# NT_MCUModule.net
KiCad netlist of a schematic drawn in EAGLE
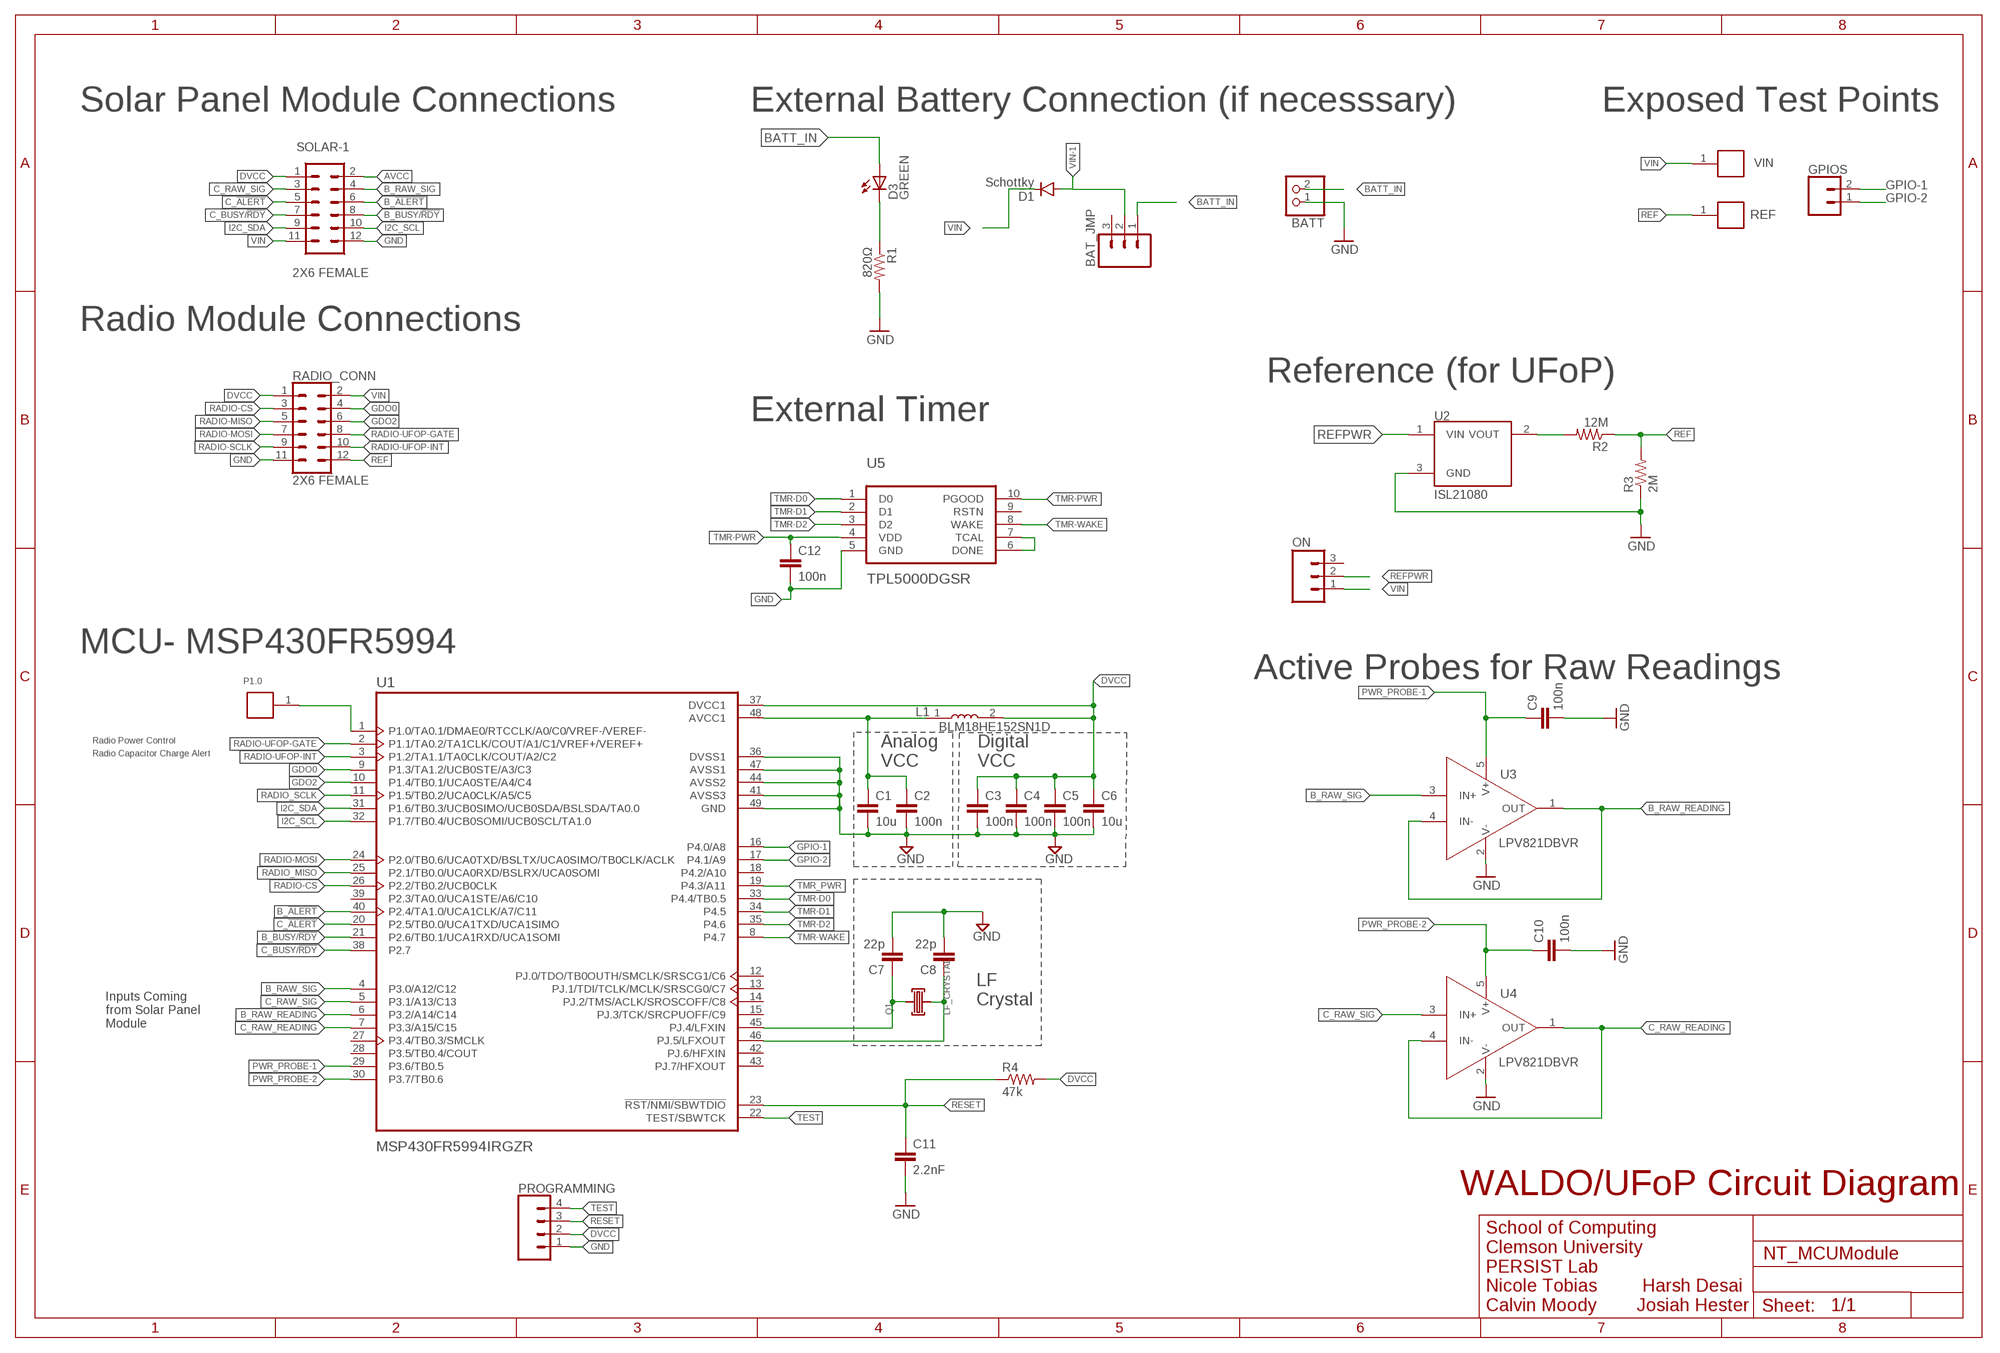
[diagram p0: schematic, sheet 1]

(export (version "E")
  (design (tool "Eeschema 10.0.6"))
  (components
    (comp (ref "BATT")
      (value "PINHD-1X2")
      (footprint "eagle-import:1X02")
      (libsource (lib "eagle-import") (part "PINHD-1X2"))
    )
    (comp (ref "BAT_JMP")
      (value "M03")
      (footprint "eagle-import:1X03-1.27MM")
      (libsource (lib "eagle-import") (part "M03"))
    )
    (comp (ref "C1")
      (value "10u")
      (footprint "eagle-import:C0603")
      (libsource (lib "eagle-import") (part "C-EUC0603"))
    )
    (comp (ref "C2")
      (value "100n")
      (footprint "eagle-import:C0603")
      (libsource (lib "eagle-import") (part "C-EUC0603"))
    )
    (comp (ref "C3")
      (value "100n")
      (footprint "eagle-import:C0603")
      (libsource (lib "eagle-import") (part "C-EUC0603"))
    )
    (comp (ref "C4")
      (value "100n")
      (footprint "eagle-import:C0603")
      (libsource (lib "eagle-import") (part "C-EUC0603"))
    )
    (comp (ref "C5")
      (value "100n")
      (footprint "eagle-import:C0603")
      (libsource (lib "eagle-import") (part "C-EUC0603"))
    )
    (comp (ref "C6")
      (value "10u")
      (footprint "eagle-import:C0603")
      (libsource (lib "eagle-import") (part "C-EUC0603"))
    )
    (comp (ref "C7")
      (value "22p")
      (footprint "eagle-import:C0603")
      (libsource (lib "eagle-import") (part "C-EUC0603"))
    )
    (comp (ref "C8")
      (value "22p")
      (footprint "eagle-import:C0603")
      (libsource (lib "eagle-import") (part "C-EUC0603"))
    )
    (comp (ref "C9")
      (value "100n")
      (footprint "eagle-import:C0603")
      (libsource (lib "eagle-import") (part "C-EUC0603"))
    )
    (comp (ref "C10")
      (value "100n")
      (footprint "eagle-import:C0603")
      (libsource (lib "eagle-import") (part "C-EUC0603"))
    )
    (comp (ref "C11")
      (value "2.2nF")
      (footprint "eagle-import:C0603")
      (libsource (lib "eagle-import") (part "C-EUC0603"))
    )
    (comp (ref "C12")
      (value "100n")
      (footprint "eagle-import:C0603")
      (libsource (lib "eagle-import") (part "C-EUC0603"))
    )
    (comp (ref "D1")
      (value "Schottky")
      (footprint "eagle-import:SOD523")
      (libsource (lib "eagle-import") (part "DIODESOD523"))
    )
    (comp (ref "D3")
      (value "GREEN")
      (footprint "eagle-import:CHIP-LED0805")
      (libsource (lib "eagle-import") (part "LEDCHIP-LED0805"))
    )
    (comp (ref "GPIOS")
      (value "CONN_02")
      (footprint "eagle-import:1X02")
      (libsource (lib "eagle-import") (part "CONN_02"))
    )
    (comp (ref "L1")
      (value "BLM18HE152SN1D")
      (footprint "eagle-import:INDC1608X95")
      (fields (field (name "DIGI-KEY_PART_NUMBER") "490-5216-1-ND") (field (name "MF") "Murata"))
      (libsource (lib "eagle-import") (part "BLM18HE152SN1D"))
    )
    (comp (ref "ON")
      (value "M03")
      (footprint "eagle-import:1X03-1.27MM")
      (libsource (lib "eagle-import") (part "M03"))
    )
    (comp (ref "P1.0")
      (value "RCU-0C")
      (footprint "eagle-import:TE_RCU-0C")
      (fields
        (field (name "COMMENT") "RCU-0C _1625854-3_")
        (field (name "MF") "TE Connectivity")
        (field (name "TOLERANCE") "0%")
      )
      (libsource (lib "eagle-import") (part "RCU-0C"))
    )
    (comp (ref "PROGRAMMING")
      (value "CONN_04")
      (footprint "eagle-import:1X04")
      (libsource (lib "eagle-import") (part "CONN_04"))
    )
    (comp (ref "Q1")
      (value "LF_CRYSTAL")
      (footprint "eagle-import:LF_CRYSTAL")
      (libsource (lib "eagle-import") (part "LF_CRYSTAL"))
    )
    (comp (ref "R1")
      (value "820Ω")
      (footprint "eagle-import:0603-RES")
      (libsource (lib "eagle-import") (part "RESISTOR0603"))
    )
    (comp (ref "R2")
      (value "12M")
      (footprint "eagle-import:0603-RES")
      (libsource (lib "eagle-import") (part "RESISTOR0603-RES"))
    )
    (comp (ref "R3")
      (value "2M")
      (footprint "eagle-import:0603-RES")
      (libsource (lib "eagle-import") (part "RESISTOR0603-RES"))
    )
    (comp (ref "R4")
      (value "47k")
      (footprint "eagle-import:0603-RES")
      (libsource (lib "eagle-import") (part "RESISTOR0603-RES"))
    )
    (comp (ref "RADIO_CONN")
      (value "2X6 FEMALE")
      (footprint "eagle-import:2X6")
      (libsource (lib "eagle-import") (part "CONN_06X2PTH_FEMALE"))
    )
    (comp (ref "REF")
      (value "RCU-0C")
      (footprint "eagle-import:TE_RCU-0C")
      (fields
        (field (name "COMMENT") "RCU-0C _1625854-3_")
        (field (name "MF") "TE Connectivity")
        (field (name "TOLERANCE") "0%")
      )
      (libsource (lib "eagle-import") (part "RCU-0C"))
    )
    (comp (ref "SOLAR-1")
      (value "2X6 FEMALE")
      (footprint "eagle-import:2X6")
      (libsource (lib "eagle-import") (part "M06X2PTH_FEMALE"))
    )
    (comp (ref "U1")
      (value "MSP430FR5994IRGZR")
      (footprint "eagle-import:QFN50P700X700X100-49N")
      (fields (field (name "MF") "Texas Instruments"))
      (libsource (lib "eagle-import") (part "MSP430FR5994IRGZR"))
    )
    (comp (ref "U2")
      (value "ISL21080")
      (footprint "eagle-import:SOT-23")
      (libsource (lib "eagle-import") (part "ISL21080"))
    )
    (comp (ref "U3")
      (value "LPV821DBVR")
      (footprint "eagle-import:SOT95P280X145-5N")
      (fields (field (name "DIGI-KEY_PART_NUMBER") "296-47911-1-ND") (field (name "MF") "Texas Instruments"))
      (libsource (lib "eagle-import") (part "LPV821DBVR"))
    )
    (comp (ref "U4")
      (value "LPV821DBVR")
      (footprint "eagle-import:SOT95P280X145-5N")
      (fields (field (name "DIGI-KEY_PART_NUMBER") "296-47911-1-ND") (field (name "MF") "Texas Instruments"))
      (libsource (lib "eagle-import") (part "LPV821DBVR"))
    )
    (comp (ref "U5")
      (value "TPL5000DGSR")
      (footprint "eagle-import:SOP50P490X110-10N")
      (fields (field (name "MF") "Texas Instruments"))
      (libsource (lib "eagle-import") (part "TPL5000DGSR"))
    )
    (comp (ref "VIN")
      (value "RCU-0C")
      (footprint "eagle-import:TE_RCU-0C")
      (fields
        (field (name "COMMENT") "RCU-0C _1625854-3_")
        (field (name "MF") "TE Connectivity")
        (field (name "TOLERANCE") "0%")
      )
      (libsource (lib "eagle-import") (part "RCU-0C"))
    )
  )
  (nets
    (net (code "1") (name "/B_BUSY{slash}~{RDY}") (class "Default")
      (node (ref "SOLAR-1") (pin "8") (pinfunction "8_8") (pintype "passive"))
      (node (ref "U1") (pin "21") (pinfunction "P2.6/TB0.1/UCA1RXD/UCA1SOMI_21") (pintype "bidirectional"))
    )
    (net (code "2") (name "/B_~{ALERT}") (class "Default")
      (node (ref "SOLAR-1") (pin "6") (pinfunction "6_6") (pintype "passive"))
      (node (ref "U1") (pin "40") (pinfunction "P2.4/TA1.0/UCA1CLK/A7/C11_40") (pintype "bidirectional"))
    )
    (net (code "3") (name "/C_BUSY{slash}~{RDY}") (class "Default")
      (node (ref "SOLAR-1") (pin "7") (pinfunction "7_7") (pintype "passive"))
      (node (ref "U1") (pin "38") (pinfunction "P2.7_38") (pintype "bidirectional"))
    )
    (net (code "4") (name "/C_~{ALERT}") (class "Default")
      (node (ref "SOLAR-1") (pin "5") (pinfunction "5_5") (pintype "passive"))
      (node (ref "U1") (pin "20") (pinfunction "P2.5/TB0.0/UCA1TXD/UCA1SIMO_20") (pintype "bidirectional"))
    )
    (net (code "5") (name "AVCC") (class "Default")
      (node (ref "C1") (pin "1") (pinfunction "1_1") (pintype "passive"))
      (node (ref "C2") (pin "1") (pinfunction "1_1") (pintype "passive"))
      (node (ref "L1") (pin "1") (pinfunction "1_1") (pintype "passive"))
      (node (ref "SOLAR-1") (pin "2") (pinfunction "2_2") (pintype "passive"))
      (node (ref "U1") (pin "48") (pinfunction "AVCC1_48") (pintype "power_in"))
    )
    (net (code "6") (name "BATT_IN") (class "Default")
      (node (ref "BATT") (pin "2") (pinfunction "2_2") (pintype "passive"))
      (node (ref "BAT_JMP") (pin "1") (pinfunction "1_1") (pintype "passive"))
      (node (ref "D3") (pin "A") (pinfunction "A_A") (pintype "passive"))
    )
    (net (code "7") (name "B_RAW_READING") (class "Default")
      (node (ref "U1") (pin "6") (pinfunction "P3.2/A14/C14_6") (pintype "bidirectional"))
      (node (ref "U3") (pin "1") (pinfunction "OUT_1") (pintype "output"))
      (node (ref "U3") (pin "4") (pinfunction "IN-_4") (pintype "input"))
    )
    (net (code "8") (name "B_RAW_SIG") (class "Default")
      (node (ref "SOLAR-1") (pin "4") (pinfunction "4_4") (pintype "passive"))
      (node (ref "U1") (pin "4") (pinfunction "P3.0/A12/C12_4") (pintype "bidirectional"))
      (node (ref "U3") (pin "3") (pinfunction "IN+_3") (pintype "input"))
    )
    (net (code "9") (name "C_RAW_READING") (class "Default")
      (node (ref "U1") (pin "7") (pinfunction "P3.3/A15/C15_7") (pintype "bidirectional"))
      (node (ref "U4") (pin "1") (pinfunction "OUT_1") (pintype "output"))
      (node (ref "U4") (pin "4") (pinfunction "IN-_4") (pintype "input"))
    )
    (net (code "10") (name "C_RAW_SIG") (class "Default")
      (node (ref "SOLAR-1") (pin "3") (pinfunction "3_3") (pintype "passive"))
      (node (ref "U1") (pin "5") (pinfunction "P3.1/A13/C13_5") (pintype "bidirectional"))
      (node (ref "U4") (pin "3") (pinfunction "IN+_3") (pintype "input"))
    )
    (net (code "11") (name "DVCC") (class "Default")
      (node (ref "C3") (pin "1") (pinfunction "1_1") (pintype "passive"))
      (node (ref "C4") (pin "1") (pinfunction "1_1") (pintype "passive"))
      (node (ref "C5") (pin "1") (pinfunction "1_1") (pintype "passive"))
      (node (ref "C6") (pin "1") (pinfunction "1_1") (pintype "passive"))
      (node (ref "L1") (pin "2") (pinfunction "2_2") (pintype "passive"))
      (node (ref "PROGRAMMING") (pin "2") (pinfunction "2_2") (pintype "passive"))
      (node (ref "R4") (pin "2") (pinfunction "2_2") (pintype "passive"))
      (node (ref "RADIO_CONN") (pin "1") (pinfunction "1_1") (pintype "passive"))
      (node (ref "SOLAR-1") (pin "1") (pinfunction "1_1") (pintype "passive"))
      (node (ref "U1") (pin "37") (pinfunction "DVCC1_37") (pintype "power_in"))
    )
    (net (code "12") (name "GDO0") (class "Default")
      (node (ref "RADIO_CONN") (pin "4") (pinfunction "4_4") (pintype "passive"))
      (node (ref "U1") (pin "9") (pinfunction "P1.3/TA1.2/UCB0STE/A3/C3_9") (pintype "bidirectional"))
    )
    (net (code "13") (name "GDO2") (class "Default")
      (node (ref "RADIO_CONN") (pin "6") (pinfunction "6_6") (pintype "passive"))
      (node (ref "U1") (pin "10") (pinfunction "P1.4/TB0.1/UCA0STE/A4/C4_10") (pintype "bidirectional"))
    )
    (net (code "14") (name "GND") (class "Default")
      (node (ref "BATT") (pin "1") (pinfunction "1_1") (pintype "passive"))
      (node (ref "C1") (pin "2") (pinfunction "2_2") (pintype "passive"))
      (node (ref "C10") (pin "2") (pinfunction "2_2") (pintype "passive"))
      (node (ref "C11") (pin "2") (pinfunction "2_2") (pintype "passive"))
      (node (ref "C12") (pin "2") (pinfunction "2_2") (pintype "passive"))
      (node (ref "C2") (pin "2") (pinfunction "2_2") (pintype "passive"))
      (node (ref "C3") (pin "2") (pinfunction "2_2") (pintype "passive"))
      (node (ref "C4") (pin "2") (pinfunction "2_2") (pintype "passive"))
      (node (ref "C5") (pin "2") (pinfunction "2_2") (pintype "passive"))
      (node (ref "C6") (pin "2") (pinfunction "2_2") (pintype "passive"))
      (node (ref "C7") (pin "2") (pinfunction "2_2") (pintype "passive"))
      (node (ref "C8") (pin "2") (pinfunction "2_2") (pintype "passive"))
      (node (ref "C9") (pin "2") (pinfunction "2_2") (pintype "passive"))
      (node (ref "PROGRAMMING") (pin "1") (pinfunction "1_1") (pintype "passive"))
      (node (ref "R1") (pin "2") (pinfunction "2_2") (pintype "passive"))
      (node (ref "R3") (pin "1") (pinfunction "1_1") (pintype "passive"))
      (node (ref "RADIO_CONN") (pin "11") (pinfunction "11_11") (pintype "passive"))
      (node (ref "SOLAR-1") (pin "12") (pinfunction "12_12") (pintype "passive"))
      (node (ref "U1") (pin "36") (pinfunction "DVSS1_36") (pintype "power_in"))
      (node (ref "U1") (pin "41") (pinfunction "AVSS3_41") (pintype "power_in"))
      (node (ref "U1") (pin "44") (pinfunction "AVSS2_44") (pintype "power_in"))
      (node (ref "U1") (pin "47") (pinfunction "AVSS1_47") (pintype "power_in"))
      (node (ref "U1") (pin "49") (pinfunction "GND_49") (pintype "power_in"))
      (node (ref "U2") (pin "3") (pinfunction "GND_3") (pintype "bidirectional"))
      (node (ref "U3") (pin "2") (pinfunction "V-_2") (pintype "power_in"))
      (node (ref "U4") (pin "2") (pinfunction "V-_2") (pintype "power_in"))
      (node (ref "U5") (pin "5") (pinfunction "GND_5") (pintype "power_in"))
    )
    (net (code "15") (name "GPIO-1") (class "Default")
      (node (ref "GPIOS") (pin "2") (pinfunction "2_2") (pintype "passive"))
      (node (ref "U1") (pin "16") (pinfunction "P4.0/A8_16") (pintype "bidirectional"))
    )
    (net (code "16") (name "GPIO-2") (class "Default")
      (node (ref "GPIOS") (pin "1") (pinfunction "1_1") (pintype "passive"))
      (node (ref "U1") (pin "17") (pinfunction "P4.1/A9_17") (pintype "bidirectional"))
    )
    (net (code "17") (name "I2C_SCL") (class "Default")
      (node (ref "SOLAR-1") (pin "10") (pinfunction "10_10") (pintype "passive"))
      (node (ref "U1") (pin "32") (pinfunction "P1.7/TB0.4/UCB0SOMI/UCB0SCL/TA1.0_32") (pintype "bidirectional"))
    )
    (net (code "18") (name "I2C_SDA") (class "Default")
      (node (ref "SOLAR-1") (pin "9") (pinfunction "9_9") (pintype "passive"))
      (node (ref "U1") (pin "31") (pinfunction "P1.6/TB0.3/UCB0SIMO/UCB0SDA/BSLSDA/TA0.0_31") (pintype "bidirectional"))
    )
    (net (code "19") (name "Net-(D3-PadC)") (class "Default")
      (node (ref "D3") (pin "C") (pinfunction "C_C") (pintype "passive"))
      (node (ref "R1") (pin "1") (pinfunction "1_1") (pintype "passive"))
    )
    (net (code "20") (name "Net-(U1-P1.0{slash}TA0.1{slash}DMAE0{slash}RTCCLK{slash}A0{slash}C0{slash}VREF-{slash}VEREF-)") (class "Default")
      (node (ref "P1.0") (pin "1") (pinfunction "1_1") (pintype "passive"))
      (node (ref "U1") (pin "1") (pinfunction "P1.0/TA0.1/DMAE0/RTCCLK/A0/C0/VREF-/VEREF-_1") (pintype "bidirectional"))
    )
    (net (code "21") (name "Net-(U1-PJ.4{slash}LFXIN)") (class "Default")
      (node (ref "C7") (pin "1") (pinfunction "1_1") (pintype "passive"))
      (node (ref "Q1") (pin "1") (pinfunction "1_1") (pintype "bidirectional"))
      (node (ref "U1") (pin "45") (pinfunction "PJ.4/LFXIN_45") (pintype "bidirectional"))
    )
    (net (code "22") (name "Net-(U1-PJ.5{slash}LFXOUT)") (class "Default")
      (node (ref "C8") (pin "1") (pinfunction "1_1") (pintype "passive"))
      (node (ref "Q1") (pin "2") (pinfunction "2_2") (pintype "bidirectional"))
      (node (ref "U1") (pin "46") (pinfunction "PJ.5/LFXOUT_46") (pintype "bidirectional"))
    )
    (net (code "23") (name "Net-(U2-VOUT)") (class "Default")
      (node (ref "R2") (pin "2") (pinfunction "2_2") (pintype "passive"))
      (node (ref "U2") (pin "2") (pinfunction "VOUT_2") (pintype "bidirectional"))
    )
    (net (code "24") (name "Net-(U5-DONE)") (class "Default")
      (node (ref "U5") (pin "6") (pinfunction "DONE_6") (pintype "input"))
      (node (ref "U5") (pin "7") (pinfunction "TCAL_7") (pintype "output"))
    )
    (net (code "25") (name "PWR_PROBE-1") (class "Default")
      (node (ref "C9") (pin "1") (pinfunction "1_1") (pintype "passive"))
      (node (ref "U1") (pin "29") (pinfunction "P3.6/TB0.5_29") (pintype "bidirectional"))
      (node (ref "U3") (pin "5") (pinfunction "V+_5") (pintype "power_in"))
    )
    (net (code "26") (name "PWR_PROBE-2") (class "Default")
      (node (ref "C10") (pin "1") (pinfunction "1_1") (pintype "passive"))
      (node (ref "U1") (pin "30") (pinfunction "P3.7/TB0.6_30") (pintype "bidirectional"))
      (node (ref "U4") (pin "5") (pinfunction "V+_5") (pintype "power_in"))
    )
    (net (code "27") (name "RADIO-CS") (class "Default")
      (node (ref "RADIO_CONN") (pin "3") (pinfunction "3_3") (pintype "passive"))
      (node (ref "U1") (pin "26") (pinfunction "P2.2/TB0.2/UCB0CLK_26") (pintype "bidirectional"))
    )
    (net (code "28") (name "RADIO-MISO") (class "Default")
      (node (ref "RADIO_CONN") (pin "5") (pinfunction "5_5") (pintype "passive"))
    )
    (net (code "29") (name "RADIO-MOSI") (class "Default")
      (node (ref "RADIO_CONN") (pin "7") (pinfunction "7_7") (pintype "passive"))
      (node (ref "U1") (pin "24") (pinfunction "P2.0/TB0.6/UCA0TXD/BSLTX/UCA0SIMO/TB0CLK/ACLK_24") (pintype "bidirectional"))
    )
    (net (code "30") (name "RADIO-SCLK") (class "Default")
      (node (ref "RADIO_CONN") (pin "9") (pinfunction "9_9") (pintype "passive"))
    )
    (net (code "31") (name "RADIO-UFOP-GATE") (class "Default")
      (node (ref "RADIO_CONN") (pin "8") (pinfunction "8_8") (pintype "passive"))
      (node (ref "U1") (pin "2") (pinfunction "P1.1/TA0.2/TA1CLK/COUT/A1/C1/VREF+/VEREF+_2") (pintype "bidirectional"))
    )
    (net (code "32") (name "RADIO-UFOP-INT") (class "Default")
      (node (ref "RADIO_CONN") (pin "10") (pinfunction "10_10") (pintype "passive"))
      (node (ref "U1") (pin "3") (pinfunction "P1.2/TA1.1/TA0CLK/COUT/A2/C2_3") (pintype "bidirectional"))
    )
    (net (code "33") (name "RADIO_MISO") (class "Default")
      (node (ref "U1") (pin "25") (pinfunction "P2.1/TB0.0/UCA0RXD/BSLRX/UCA0SOMI_25") (pintype "bidirectional"))
    )
    (net (code "34") (name "RADIO_SCLK") (class "Default")
      (node (ref "U1") (pin "11") (pinfunction "P1.5/TB0.2/UCA0CLK/A5/C5_11") (pintype "bidirectional"))
    )
    (net (code "35") (name "REF") (class "Default")
      (node (ref "R2") (pin "1") (pinfunction "1_1") (pintype "passive"))
      (node (ref "R3") (pin "2") (pinfunction "2_2") (pintype "passive"))
      (node (ref "RADIO_CONN") (pin "12") (pinfunction "12_12") (pintype "passive"))
      (node (ref "REF") (pin "1") (pinfunction "1_1") (pintype "passive"))
    )
    (net (code "36") (name "REFPWR") (class "Default")
      (node (ref "ON") (pin "2") (pinfunction "2_2") (pintype "passive"))
      (node (ref "U2") (pin "1") (pinfunction "VIN_1") (pintype "bidirectional"))
    )
    (net (code "37") (name "RESET") (class "Default")
      (node (ref "C11") (pin "1") (pinfunction "1_1") (pintype "passive"))
      (node (ref "PROGRAMMING") (pin "3") (pinfunction "3_3") (pintype "passive"))
      (node (ref "R4") (pin "1") (pinfunction "1_1") (pintype "passive"))
      (node (ref "U1") (pin "23") (pinfunction "~{RST/NMI/SBWTDIO}_23") (pintype "bidirectional"))
    )
    (net (code "38") (name "TEST") (class "Default")
      (node (ref "PROGRAMMING") (pin "4") (pinfunction "4_4") (pintype "passive"))
      (node (ref "U1") (pin "22") (pinfunction "TEST/SBWTCK_22") (pintype "bidirectional"))
    )
    (net (code "39") (name "TMR-D0") (class "Default")
      (node (ref "U1") (pin "33") (pinfunction "P4.4/TB0.5_33") (pintype "bidirectional"))
      (node (ref "U5") (pin "1") (pinfunction "D0_1") (pintype "input"))
    )
    (net (code "40") (name "TMR-D1") (class "Default")
      (node (ref "U1") (pin "34") (pinfunction "P4.5_34") (pintype "bidirectional"))
      (node (ref "U5") (pin "2") (pinfunction "D1_2") (pintype "input"))
    )
    (net (code "41") (name "TMR-D2") (class "Default")
      (node (ref "U1") (pin "35") (pinfunction "P4.6_35") (pintype "bidirectional"))
      (node (ref "U5") (pin "3") (pinfunction "D2_3") (pintype "input"))
    )
    (net (code "42") (name "TMR-PWR") (class "Default")
      (node (ref "C12") (pin "1") (pinfunction "1_1") (pintype "passive"))
      (node (ref "U5") (pin "10") (pinfunction "PGOOD_10") (pintype "bidirectional"))
      (node (ref "U5") (pin "4") (pinfunction "VDD_4") (pintype "power_in"))
    )
    (net (code "43") (name "TMR-WAKE") (class "Default")
      (node (ref "U1") (pin "8") (pinfunction "P4.7_8") (pintype "bidirectional"))
      (node (ref "U5") (pin "8") (pinfunction "WAKE_8") (pintype "output"))
    )
    (net (code "44") (name "TMR_PWR") (class "Default")
      (node (ref "U1") (pin "19") (pinfunction "P4.3/A11_19") (pintype "bidirectional"))
    )
    (net (code "45") (name "VIN") (class "Default")
      (node (ref "D1") (pin "C") (pinfunction "C_C") (pintype "passive"))
      (node (ref "ON") (pin "1") (pinfunction "1_1") (pintype "passive"))
      (node (ref "RADIO_CONN") (pin "2") (pinfunction "2_2") (pintype "passive"))
      (node (ref "SOLAR-1") (pin "11") (pinfunction "11_11") (pintype "passive"))
      (node (ref "VIN") (pin "1") (pinfunction "1_1") (pintype "passive"))
    )
    (net (code "46") (name "VIN-1") (class "Default")
      (node (ref "BAT_JMP") (pin "2") (pinfunction "2_2") (pintype "passive"))
      (node (ref "D1") (pin "A") (pinfunction "A_A") (pintype "passive"))
    )
    (net (code "47") (name "unconnected-(BAT_JMP-Pad3)") (class "Default")
      (node (ref "BAT_JMP") (pin "3") (pinfunction "3_3") (pintype "passive"))
    )
    (net (code "48") (name "unconnected-(ON-Pad3)") (class "Default")
      (node (ref "ON") (pin "3") (pinfunction "3_3") (pintype "passive"))
    )
    (net (code "49") (name "unconnected-(U1-P2.3{slash}TA0.0{slash}UCA1STE{slash}A6{slash}C10-Pad39)") (class "Default")
      (node (ref "U1") (pin "39") (pinfunction "P2.3/TA0.0/UCA1STE/A6/C10_39") (pintype "bidirectional"))
    )
    (net (code "50") (name "unconnected-(U1-P3.4{slash}TB0.3{slash}SMCLK-Pad27)") (class "Default")
      (node (ref "U1") (pin "27") (pinfunction "P3.4/TB0.3/SMCLK_27") (pintype "bidirectional"))
    )
    (net (code "51") (name "unconnected-(U1-P3.5{slash}TB0.4{slash}COUT-Pad28)") (class "Default")
      (node (ref "U1") (pin "28") (pinfunction "P3.5/TB0.4/COUT_28") (pintype "bidirectional"))
    )
    (net (code "52") (name "unconnected-(U1-P4.2{slash}A10-Pad18)") (class "Default")
      (node (ref "U1") (pin "18") (pinfunction "P4.2/A10_18") (pintype "bidirectional"))
    )
    (net (code "53") (name "unconnected-(U1-PJ.0{slash}TDO{slash}TB0OUTH{slash}SMCLK{slash}SRSCG1{slash}C6-Pad12)") (class "Default")
      (node (ref "U1") (pin "12") (pinfunction "PJ.0/TDO/TB0OUTH/SMCLK/SRSCG1/C6_12") (pintype "bidirectional"))
    )
    (net (code "54") (name "unconnected-(U1-PJ.1{slash}TDI{slash}TCLK{slash}MCLK{slash}SRSCG0{slash}C7-Pad13)") (class "Default")
      (node (ref "U1") (pin "13") (pinfunction "PJ.1/TDI/TCLK/MCLK/SRSCG0/C7_13") (pintype "bidirectional"))
    )
    (net (code "55") (name "unconnected-(U1-PJ.2{slash}TMS{slash}ACLK{slash}SROSCOFF{slash}C8-Pad14)") (class "Default")
      (node (ref "U1") (pin "14") (pinfunction "PJ.2/TMS/ACLK/SROSCOFF/C8_14") (pintype "bidirectional"))
    )
    (net (code "56") (name "unconnected-(U1-PJ.3{slash}TCK{slash}SRCPUOFF{slash}C9-Pad15)") (class "Default")
      (node (ref "U1") (pin "15") (pinfunction "PJ.3/TCK/SRCPUOFF/C9_15") (pintype "bidirectional"))
    )
    (net (code "57") (name "unconnected-(U1-PJ.6{slash}HFXIN-Pad42)") (class "Default")
      (node (ref "U1") (pin "42") (pinfunction "PJ.6/HFXIN_42") (pintype "bidirectional"))
    )
    (net (code "58") (name "unconnected-(U1-PJ.7{slash}HFXOUT-Pad43)") (class "Default")
      (node (ref "U1") (pin "43") (pinfunction "PJ.7/HFXOUT_43") (pintype "bidirectional"))
    )
    (net (code "59") (name "unconnected-(U5-RSTN-Pad9)") (class "Default")
      (node (ref "U5") (pin "9") (pinfunction "RSTN_9") (pintype "input"))
    )
  )
)
